# SCH_lhal_2024-10-11.net
KiCad netlist of a schematic drawn in EasyEDA
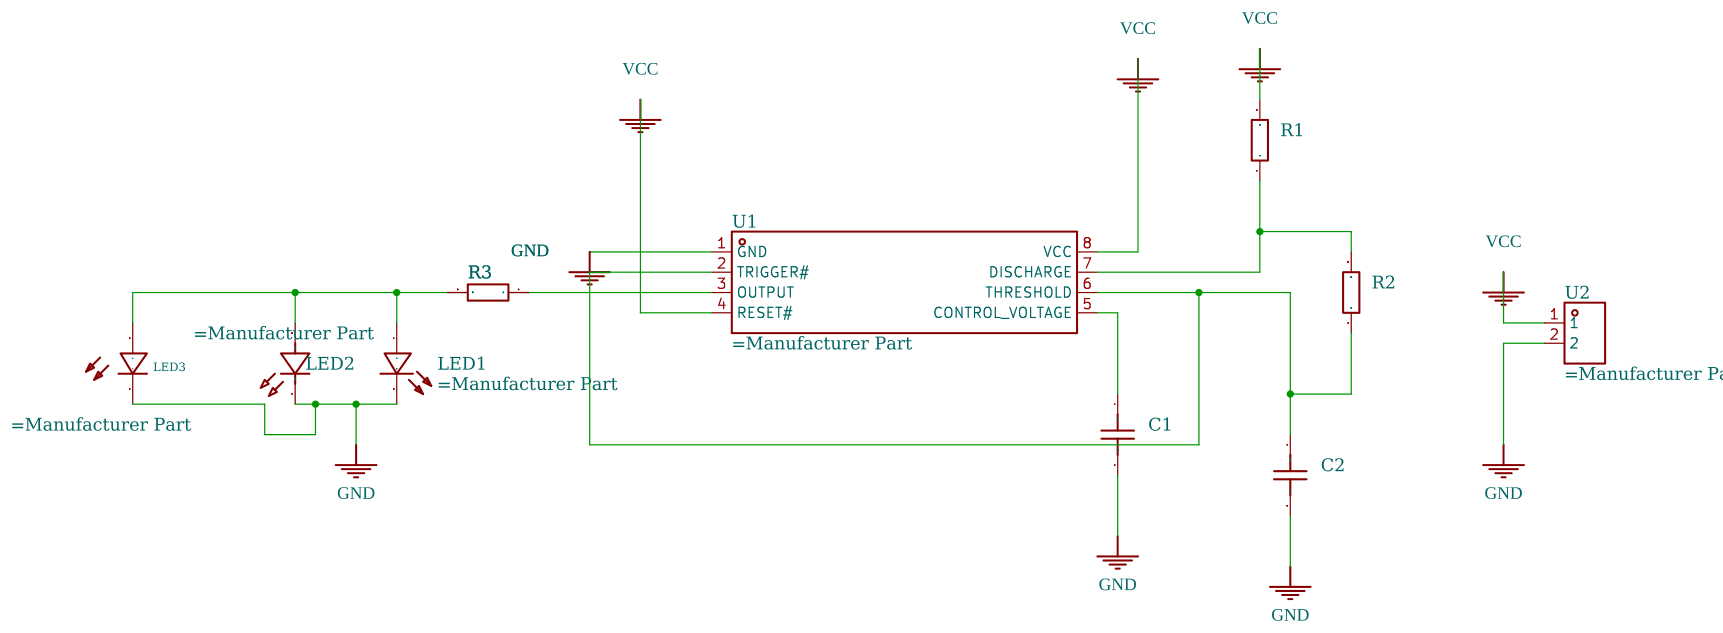
[diagram p0: schematic sheet]

(export (version "E")
  (design (tool "Eeschema 10.0.6"))
  (components
    (comp (ref "C1") (value "0.1u") (libsource (lib "") (part "Unknown_715_-440")))
    (comp (ref "C2") (value "100uf") (libsource (lib "") (part "Unknown_800_-420")))
    (comp (ref "LED1")
      (value "=Manufacturer Part")
      (fields
        (field (name "Manufacturer Part") "DY-204URC/SN-A3(EL)")
        (field (name "Manufacturer") "TONYU(东裕)")
      )
      (libsource (lib "") (part "Unknown_360_-475"))
    )
    (comp (ref "LED2")
      (value "=Manufacturer Part")
      (fields
        (field (name "Manufacturer Part") "TJ-S1005CL4T5ALC6B-A5")
        (field (name "Manufacturer") "TOGIALED(统佳)")
      )
      (libsource (lib "") (part "Unknown_310_-475"))
    )
    (comp (ref "LED3")
      (value "=Manufacturer Part")
      (fields
        (field (name "Manufacturer Part") "LTST-C281KFKT-5A")
        (field (name "Manufacturer") "LITEON(光宝)")
      )
      (libsource (lib "") (part "Unknown_230_-475"))
    )
    (comp (ref "R1") (value "5.6K") (libsource (lib "") (part "Unknown_785_-585")))
    (comp (ref "R2") (value "22K") (libsource (lib "") (part "Unknown_830_-510")))
    (comp (ref "R3") (value "1K") (libsource (lib "") (part "Unknown_405_-510")))
    (comp (ref "U1")
      (value "=Manufacturer Part")
      (fields (field (name "Manufacturer Part") "NE555D") (field (name "Manufacturer") "HTC"))
      (libsource (lib "") (part "Unknown_610_-515"))
    )
    (comp (ref "U2")
      (value "=Manufacturer Part")
      (fields
        (field (name "Manufacturer Part") "ZX-PZ2.54-1-2PZZ")
        (field (name "Manufacturer") "Megastar(兆星)")
      )
      (libsource (lib "") (part "Unknown_945_-490"))
    )
  )
  (nets
    (net (code "1") (name "GND") (class "Default")
      (node (ref "C1") (pin "2") (pinfunction "2_2") (pintype "unspecified"))
      (node (ref "C2") (pin "2") (pinfunction "2_2") (pintype "unspecified"))
      (node (ref "LED1") (pin "2") (pinfunction "K_2") (pintype "unspecified"))
      (node (ref "LED2") (pin "1") (pinfunction "K_1") (pintype "unspecified"))
      (node (ref "LED3") (pin "1") (pinfunction "-_1") (pintype "unspecified"))
      (node (ref "U1") (pin "1") (pinfunction "GND_1") (pintype "unspecified"))
      (node (ref "U2") (pin "2") (pinfunction "2_2") (pintype "unspecified"))
    )
    (net (code "2") (name "Net-(LED1-A)") (class "Default")
      (node (ref "LED1") (pin "1") (pinfunction "A_1") (pintype "unspecified"))
      (node (ref "LED2") (pin "2") (pinfunction "A_2") (pintype "unspecified"))
      (node (ref "LED3") (pin "2") (pinfunction "+_2") (pintype "unspecified"))
      (node (ref "R3") (pin "2") (pinfunction "2_2") (pintype "unspecified"))
    )
    (net (code "3") (name "Net-(U1-CONTROL_VOLTAGE)") (class "Default")
      (node (ref "C1") (pin "1") (pinfunction "1_1") (pintype "unspecified"))
      (node (ref "U1") (pin "5") (pinfunction "CONTROL_VOLTAGE_5") (pintype "unspecified"))
    )
    (net (code "4") (name "Net-(U1-DISCHARGE)") (class "Default")
      (node (ref "R1") (pin "1") (pinfunction "1_1") (pintype "unspecified"))
      (node (ref "R2") (pin "2") (pinfunction "2_2") (pintype "unspecified"))
      (node (ref "U1") (pin "7") (pinfunction "DISCHARGE_7") (pintype "unspecified"))
    )
    (net (code "5") (name "Net-(U1-OUTPUT)") (class "Default")
      (node (ref "R3") (pin "1") (pinfunction "1_1") (pintype "unspecified"))
      (node (ref "U1") (pin "3") (pinfunction "OUTPUT_3") (pintype "unspecified"))
    )
    (net (code "6") (name "Net-(U1-THRESHOLD)") (class "Default")
      (node (ref "C2") (pin "1") (pinfunction "1_1") (pintype "unspecified"))
      (node (ref "R2") (pin "1") (pinfunction "1_1") (pintype "unspecified"))
      (node (ref "U1") (pin "2") (pinfunction "TRIGGER#_2") (pintype "unspecified"))
      (node (ref "U1") (pin "6") (pinfunction "THRESHOLD_6") (pintype "unspecified"))
    )
    (net (code "7") (name "VCC") (class "Default")
      (node (ref "R1") (pin "2") (pinfunction "2_2") (pintype "unspecified"))
      (node (ref "U1") (pin "4") (pinfunction "RESET#_4") (pintype "unspecified"))
      (node (ref "U1") (pin "8") (pinfunction "VCC_8") (pintype "unspecified"))
      (node (ref "U2") (pin "1") (pinfunction "1_1") (pintype "unspecified"))
    )
  )
)
